# sensors.net
KiCad netlist of a schematic drawn in EAGLE
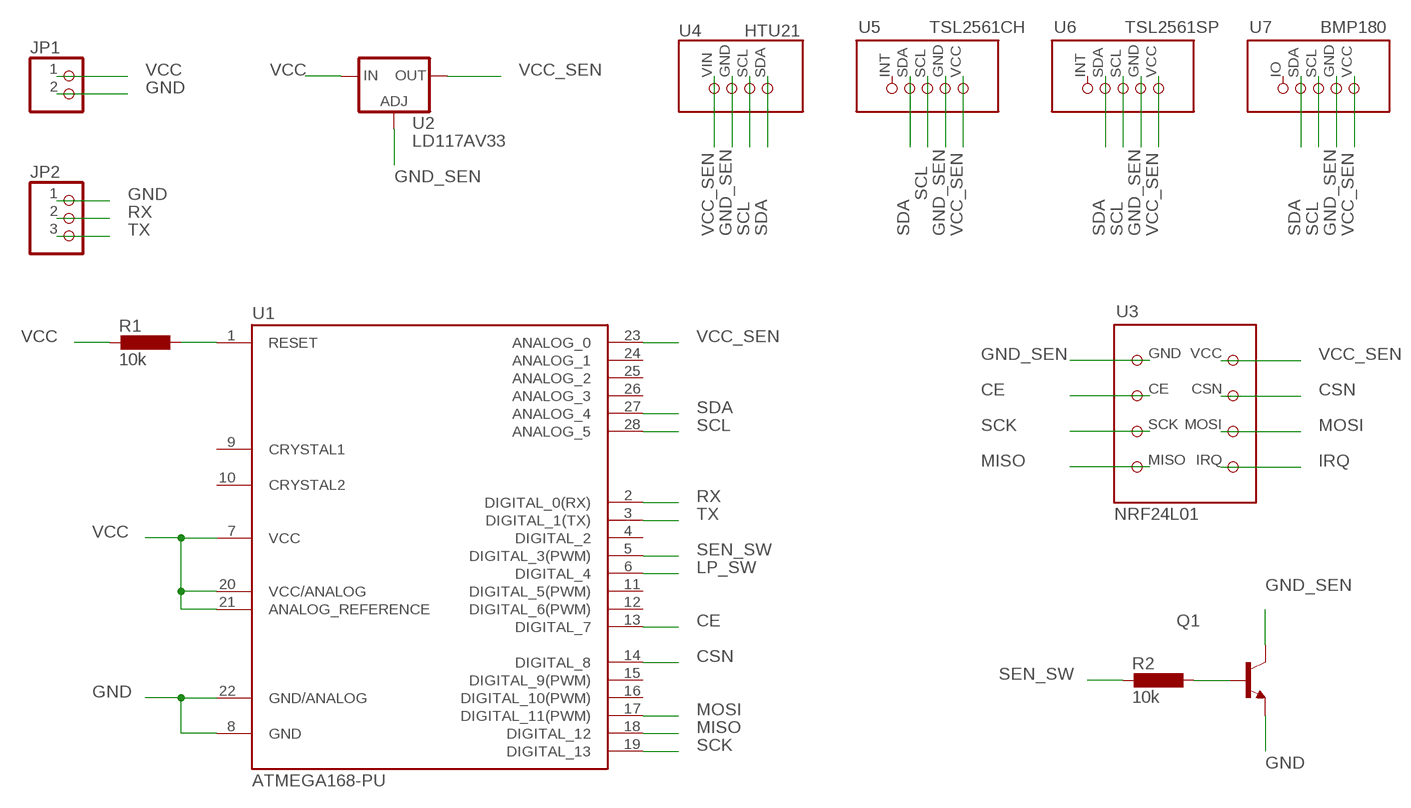
[diagram p0: schematic, sheet 1]

(export (version "E")
  (design (tool "Eeschema 10.0.6"))
  (components
    (comp (ref "JP1")
      (value "PINHD-1X2")
      (footprint "eagle-import:1X02")
      (libsource (lib "eagle-import") (part "PINHD-1X2"))
    )
    (comp (ref "JP2")
      (value "PINHD-1X3")
      (footprint "eagle-import:1X03")
      (libsource (lib "eagle-import") (part "PINHD-1X3"))
    )
    (comp (ref "Q1")
      (value "-NPN-TO92-EBC")
      (footprint "eagle-import:TO92-EBC")
      (libsource (lib "eagle-import") (part "-NPN-TO92-EBC"))
    )
    (comp (ref "R1")
      (value "10k")
      (footprint "eagle-import:0207_10")
      (libsource (lib "eagle-import") (part "L-EU0207/10"))
    )
    (comp (ref "R2")
      (value "10k")
      (footprint "eagle-import:0207_10")
      (libsource (lib "eagle-import") (part "L-EU0207/10"))
    )
    (comp (ref "U1")
      (value "ATMEGA168-PU")
      (footprint "eagle-import:DIL28-3")
      (libsource (lib "eagle-import") (part "ATMEGA168-PU"))
    )
    (comp (ref "U2")
      (value "LD117AV33")
      (footprint "eagle-import:TO220L1")
      (libsource (lib "eagle-import") (part "LD117A?V33"))
    )
    (comp (ref "U3")
      (value "NRF24L01")
      (footprint "eagle-import:NRF24L01")
      (libsource (lib "eagle-import") (part "NRF24L01"))
    )
    (comp (ref "U4")
      (value "HTU21")
      (footprint "eagle-import:HTU21")
      (libsource (lib "eagle-import") (part "HTU21"))
    )
    (comp (ref "U5")
      (value "TSL2561CH")
      (footprint "eagle-import:TSL2561-CH")
      (libsource (lib "eagle-import") (part "TSL2561CH"))
    )
    (comp (ref "U6")
      (value "TSL2561SP")
      (footprint "eagle-import:TSL2561-SP")
      (libsource (lib "eagle-import") (part "TSL2561SP"))
    )
    (comp (ref "U7")
      (value "BMP180")
      (footprint "eagle-import:BMP180")
      (libsource (lib "eagle-import") (part "BMP180"))
    )
  )
  (nets
    (net (code "1") (name "/CE") (class "Default")
      (node (ref "U1") (pin "13") (pinfunction "DIGITAL_7_13") (pintype "bidirectional"))
      (node (ref "U3") (pin "CE") (pinfunction "CE_CE") (pintype "passive"))
    )
    (net (code "2") (name "/CSN") (class "Default")
      (node (ref "U1") (pin "14") (pinfunction "DIGITAL_8_14") (pintype "bidirectional"))
      (node (ref "U3") (pin "CSN") (pinfunction "CSN_CSN") (pintype "passive"))
    )
    (net (code "3") (name "/GND") (class "Default")
      (node (ref "JP1") (pin "2") (pinfunction "2_2") (pintype "passive"))
      (node (ref "JP2") (pin "1") (pinfunction "1_1") (pintype "passive"))
      (node (ref "Q1") (pin "E") (pinfunction "E_E") (pintype "passive"))
      (node (ref "U1") (pin "22") (pinfunction "GND/ANALOG_22") (pintype "power_in"))
      (node (ref "U1") (pin "8") (pinfunction "GND_8") (pintype "power_in"))
    )
    (net (code "4") (name "/GND_SEN") (class "Default")
      (node (ref "Q1") (pin "C") (pinfunction "C_C") (pintype "passive"))
      (node (ref "U2") (pin "1") (pinfunction "ADJ_1") (pintype "input"))
      (node (ref "U3") (pin "GND") (pinfunction "GND_GND") (pintype "passive"))
      (node (ref "U4") (pin "GND") (pinfunction "GND_GND") (pintype "passive"))
      (node (ref "U5") (pin "GND") (pinfunction "GND_GND") (pintype "passive"))
      (node (ref "U6") (pin "GND") (pinfunction "GND_GND") (pintype "passive"))
      (node (ref "U7") (pin "GND") (pinfunction "GND_GND") (pintype "passive"))
    )
    (net (code "5") (name "/IRQ") (class "Default")
      (node (ref "U3") (pin "IRQ") (pinfunction "IRQ_IRQ") (pintype "passive"))
    )
    (net (code "6") (name "/LP_SW") (class "Default")
      (node (ref "U1") (pin "6") (pinfunction "DIGITAL_4_6") (pintype "bidirectional"))
    )
    (net (code "7") (name "/MISO") (class "Default")
      (node (ref "U1") (pin "18") (pinfunction "DIGITAL_12_18") (pintype "bidirectional"))
      (node (ref "U3") (pin "MISO") (pinfunction "MISO_MISO") (pintype "passive"))
    )
    (net (code "8") (name "/MOSI") (class "Default")
      (node (ref "U1") (pin "17") (pinfunction "DIGITAL_11(PWM)_17") (pintype "bidirectional"))
      (node (ref "U3") (pin "MOSI") (pinfunction "MOSI_MOSI") (pintype "passive"))
    )
    (net (code "9") (name "/RX") (class "Default")
      (node (ref "JP2") (pin "2") (pinfunction "2_2") (pintype "passive"))
      (node (ref "U1") (pin "2") (pinfunction "DIGITAL_0(RX)_2") (pintype "bidirectional"))
    )
    (net (code "10") (name "/SCK") (class "Default")
      (node (ref "U1") (pin "19") (pinfunction "DIGITAL_13_19") (pintype "bidirectional"))
      (node (ref "U3") (pin "SCK") (pinfunction "SCK_SCK") (pintype "passive"))
    )
    (net (code "11") (name "/SCL") (class "Default")
      (node (ref "U1") (pin "28") (pinfunction "ANALOG_5_28") (pintype "bidirectional"))
      (node (ref "U4") (pin "SCL") (pinfunction "SCL_SCL") (pintype "passive"))
      (node (ref "U5") (pin "SCL") (pinfunction "SCL_SCL") (pintype "passive"))
      (node (ref "U6") (pin "SCL") (pinfunction "SCL_SCL") (pintype "passive"))
      (node (ref "U7") (pin "SCL") (pinfunction "SCL_SCL") (pintype "passive"))
    )
    (net (code "12") (name "/SDA") (class "Default")
      (node (ref "U1") (pin "27") (pinfunction "ANALOG_4_27") (pintype "bidirectional"))
      (node (ref "U4") (pin "SDA") (pinfunction "SDA_SDA") (pintype "passive"))
      (node (ref "U5") (pin "SDA") (pinfunction "SDA_SDA") (pintype "passive"))
      (node (ref "U6") (pin "SDA") (pinfunction "SDA_SDA") (pintype "passive"))
      (node (ref "U7") (pin "SDA") (pinfunction "SDA_SDA") (pintype "passive"))
    )
    (net (code "13") (name "/SEN_SW") (class "Default")
      (node (ref "R2") (pin "2") (pinfunction "2_2") (pintype "passive"))
      (node (ref "U1") (pin "5") (pinfunction "DIGITAL_3(PWM)_5") (pintype "bidirectional"))
    )
    (net (code "14") (name "/TX") (class "Default")
      (node (ref "JP2") (pin "3") (pinfunction "3_3") (pintype "passive"))
      (node (ref "U1") (pin "3") (pinfunction "DIGITAL_1(TX)_3") (pintype "bidirectional"))
    )
    (net (code "15") (name "/VCC") (class "Default")
      (node (ref "JP1") (pin "1") (pinfunction "1_1") (pintype "passive"))
      (node (ref "R1") (pin "2") (pinfunction "2_2") (pintype "passive"))
      (node (ref "U1") (pin "20") (pinfunction "VCC/ANALOG_20") (pintype "passive"))
      (node (ref "U1") (pin "21") (pinfunction "ANALOG_REFERENCE_21") (pintype "passive"))
      (node (ref "U1") (pin "7") (pinfunction "VCC_7") (pintype "power_in"))
      (node (ref "U2") (pin "3") (pinfunction "IN_3") (pintype "input"))
    )
    (net (code "16") (name "/VCC_SEN") (class "Default")
      (node (ref "U1") (pin "23") (pinfunction "ANALOG_0_23") (pintype "bidirectional"))
      (node (ref "U2") (pin "2") (pinfunction "OUT_2") (pintype "passive"))
      (node (ref "U3") (pin "VCC") (pinfunction "VCC_VCC") (pintype "passive"))
      (node (ref "U4") (pin "VIN") (pinfunction "VIN_VIN") (pintype "passive"))
      (node (ref "U5") (pin "VCC") (pinfunction "VCC_VCC") (pintype "passive"))
      (node (ref "U6") (pin "VCC") (pinfunction "VCC_VCC") (pintype "passive"))
      (node (ref "U7") (pin "VCC") (pinfunction "VCC_VCC") (pintype "passive"))
    )
    (net (code "17") (name "Net-(Q1-PadB)") (class "Default")
      (node (ref "Q1") (pin "B") (pinfunction "B_B") (pintype "passive"))
      (node (ref "R2") (pin "1") (pinfunction "1_1") (pintype "passive"))
    )
    (net (code "18") (name "Net-(U1-RESET)") (class "Default")
      (node (ref "R1") (pin "1") (pinfunction "1_1") (pintype "passive"))
      (node (ref "U1") (pin "1") (pinfunction "RESET_1") (pintype "bidirectional"))
    )
    (net (code "19") (name "unconnected-(U1-ANALOG_1-Pad24)") (class "Default")
      (node (ref "U1") (pin "24") (pinfunction "ANALOG_1_24") (pintype "bidirectional"))
    )
    (net (code "20") (name "unconnected-(U1-ANALOG_2-Pad25)") (class "Default")
      (node (ref "U1") (pin "25") (pinfunction "ANALOG_2_25") (pintype "bidirectional"))
    )
    (net (code "21") (name "unconnected-(U1-ANALOG_3-Pad26)") (class "Default")
      (node (ref "U1") (pin "26") (pinfunction "ANALOG_3_26") (pintype "bidirectional"))
    )
    (net (code "22") (name "unconnected-(U1-CRYSTAL1-Pad9)") (class "Default")
      (node (ref "U1") (pin "9") (pinfunction "CRYSTAL1_9") (pintype "bidirectional"))
    )
    (net (code "23") (name "unconnected-(U1-CRYSTAL2-Pad10)") (class "Default")
      (node (ref "U1") (pin "10") (pinfunction "CRYSTAL2_10") (pintype "bidirectional"))
    )
    (net (code "24") (name "unconnected-(U1-DIGITAL_2-Pad4)") (class "Default")
      (node (ref "U1") (pin "4") (pinfunction "DIGITAL_2_4") (pintype "bidirectional"))
    )
    (net (code "25") (name "unconnected-(U1-DIGITAL_5(PWM)-Pad11)") (class "Default")
      (node (ref "U1") (pin "11") (pinfunction "DIGITAL_5(PWM)_11") (pintype "bidirectional"))
    )
    (net (code "26") (name "unconnected-(U1-DIGITAL_6(PWM)-Pad12)") (class "Default")
      (node (ref "U1") (pin "12") (pinfunction "DIGITAL_6(PWM)_12") (pintype "bidirectional"))
    )
    (net (code "27") (name "unconnected-(U1-DIGITAL_9(PWM)-Pad15)") (class "Default")
      (node (ref "U1") (pin "15") (pinfunction "DIGITAL_9(PWM)_15") (pintype "bidirectional"))
    )
    (net (code "28") (name "unconnected-(U1-DIGITAL_10(PWM)-Pad16)") (class "Default")
      (node (ref "U1") (pin "16") (pinfunction "DIGITAL_10(PWM)_16") (pintype "bidirectional"))
    )
    (net (code "29") (name "unconnected-(U5-PadINT)") (class "Default")
      (node (ref "U5") (pin "INT") (pinfunction "INT_INT") (pintype "passive"))
    )
    (net (code "30") (name "unconnected-(U6-PadINT)") (class "Default")
      (node (ref "U6") (pin "INT") (pinfunction "INT_INT") (pintype "passive"))
    )
    (net (code "31") (name "unconnected-(U7-INT-PadIO)") (class "Default")
      (node (ref "U7") (pin "IO") (pinfunction "INT_IO") (pintype "passive"))
    )
  )
)
